# water_level.net
KiCad netlist of a schematic drawn in EAGLE
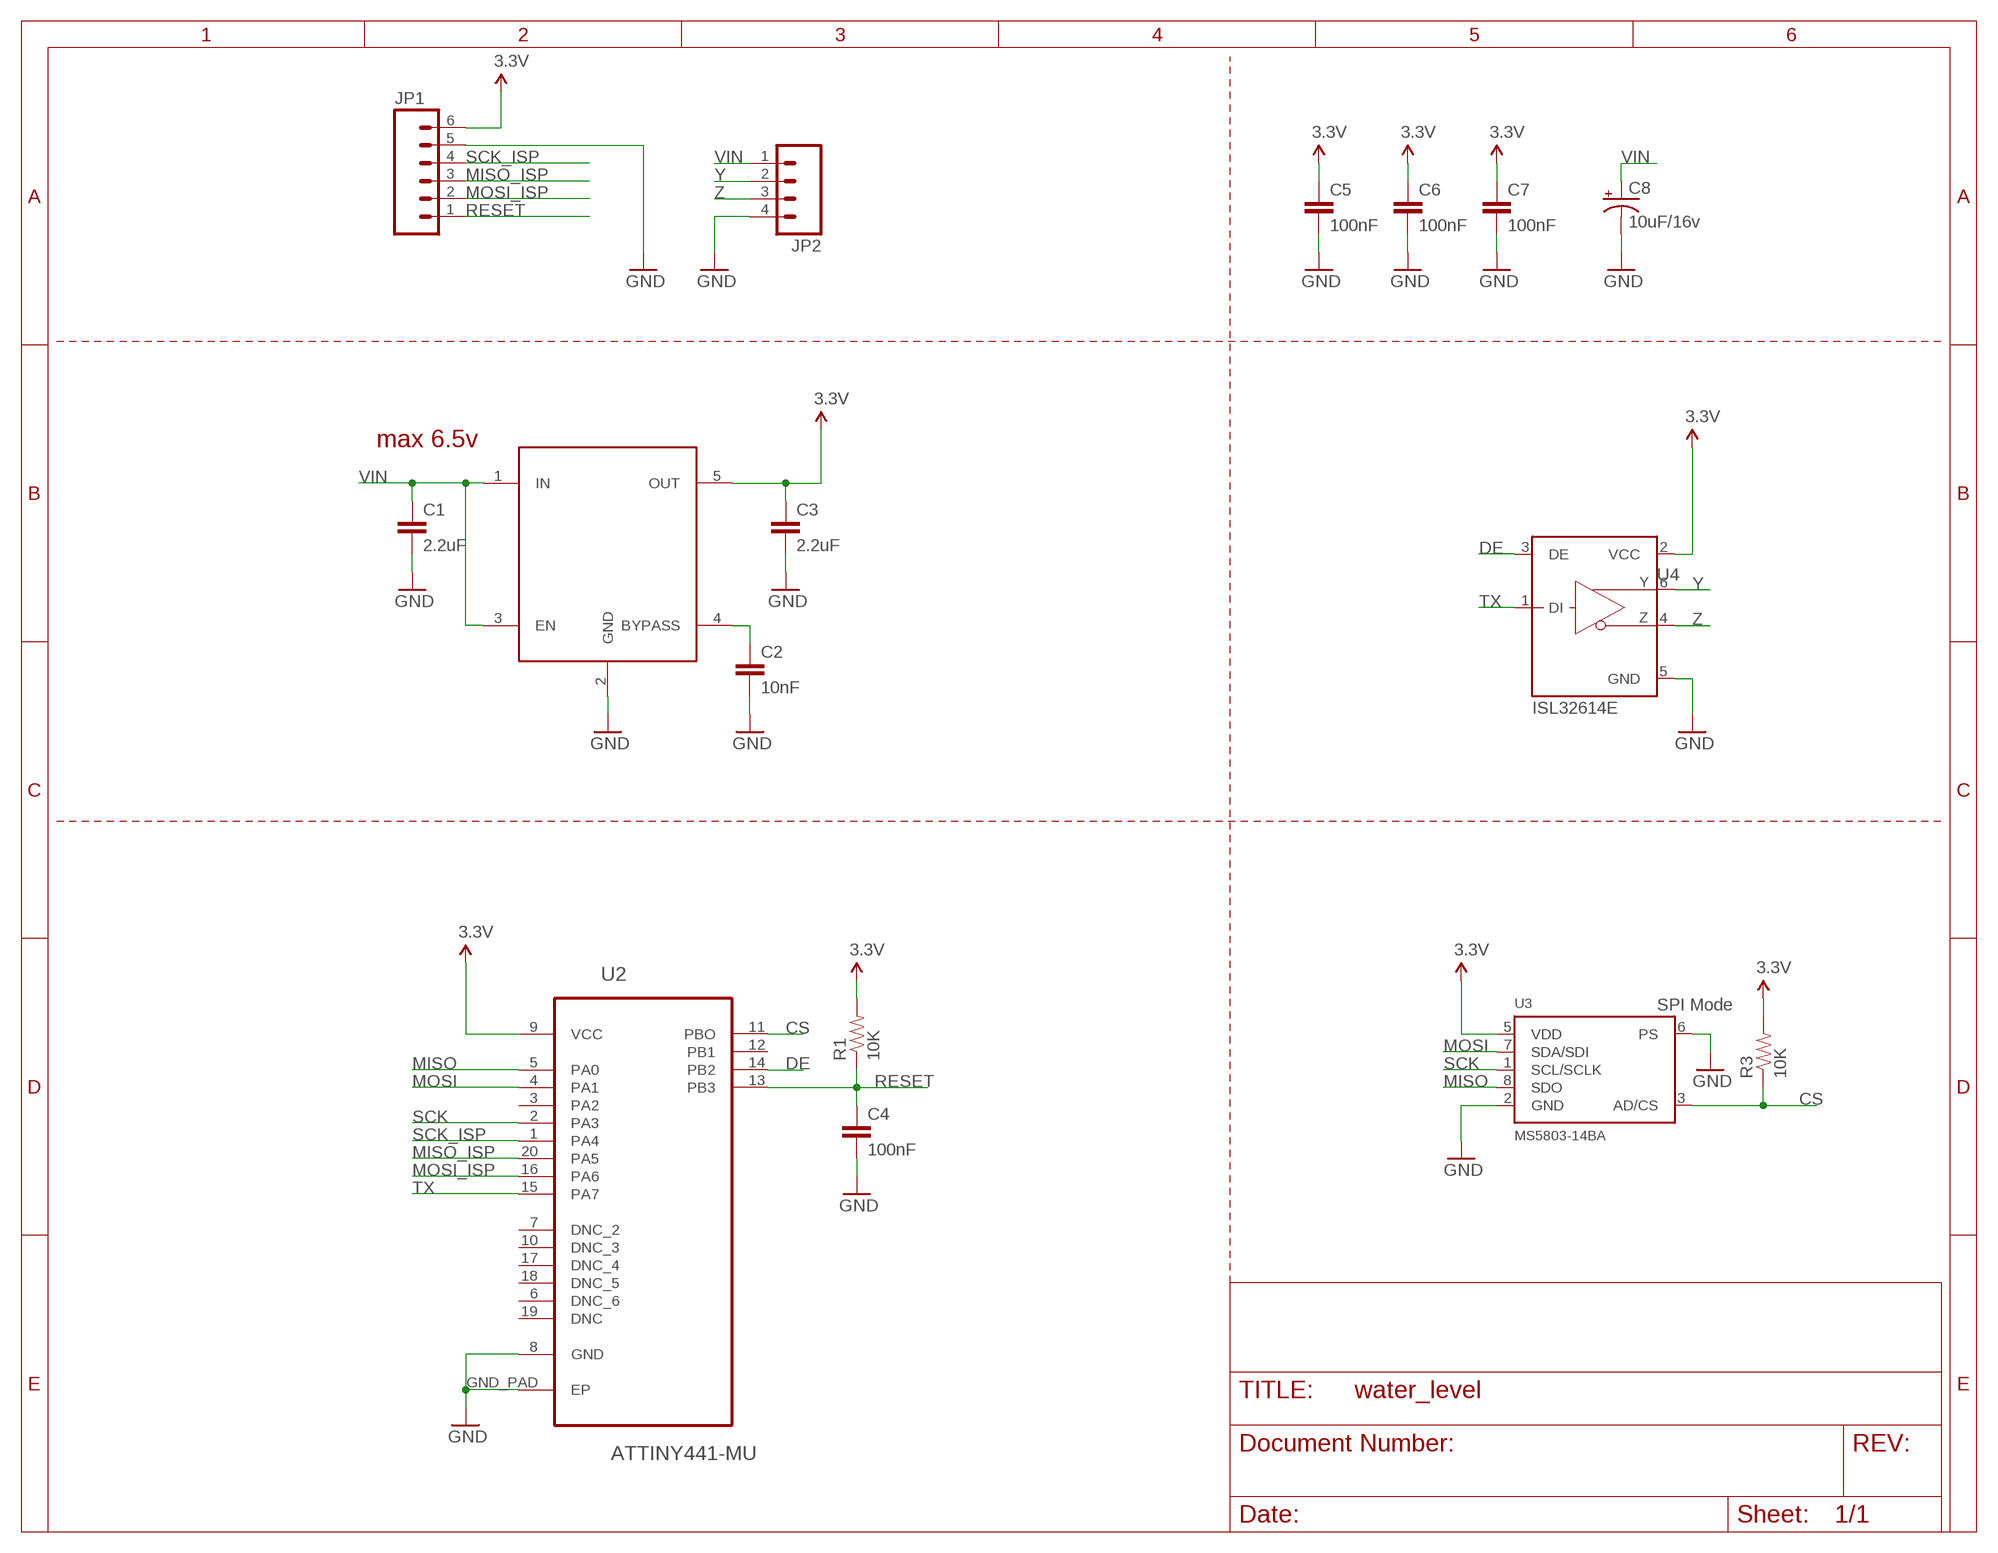
[diagram p0: schematic, sheet 1]

(export (version "E")
  (design (tool "Eeschema 10.0.6"))
  (components
    (comp (ref "C1")
      (value "2.2uF")
      (footprint "eagle-import:0402-CAP")
      (libsource (lib "eagle-import") (part "CAP0402-CAP"))
    )
    (comp (ref "C2")
      (value "10nF")
      (footprint "eagle-import:0402-CAP")
      (libsource (lib "eagle-import") (part "CAP0402-CAP"))
    )
    (comp (ref "C3")
      (value "2.2uF")
      (footprint "eagle-import:0402-CAP")
      (libsource (lib "eagle-import") (part "CAP0402-CAP"))
    )
    (comp (ref "C4")
      (value "100nF")
      (footprint "eagle-import:0402-CAP")
      (libsource (lib "eagle-import") (part "CAP0402-CAP"))
    )
    (comp (ref "C5")
      (value "100nF")
      (footprint "eagle-import:0402-CAP")
      (libsource (lib "eagle-import") (part "CAP0402-CAP"))
    )
    (comp (ref "C6")
      (value "100nF")
      (footprint "eagle-import:0402-CAP")
      (libsource (lib "eagle-import") (part "CAP0402-CAP"))
    )
    (comp (ref "C7")
      (value "100nF")
      (footprint "eagle-import:0402-CAP")
      (libsource (lib "eagle-import") (part "CAP0402-CAP"))
    )
    (comp (ref "C8")
      (value "10uF/16v")
      (footprint "eagle-import:EIA3216")
      (libsource (lib "eagle-import") (part "10UF-16V-10%(TANT)"))
    )
    (comp (ref "JP1")
      (value "M06SILK_FEMALE_PTH")
      (footprint "eagle-import:1X06")
      (libsource (lib "eagle-import") (part "M06SILK_FEMALE_PTH"))
    )
    (comp (ref "JP2")
      (value "M04PTH")
      (footprint "eagle-import:1X04")
      (libsource (lib "eagle-import") (part "M04PTH"))
    )
    (comp (ref "R1")
      (value "10K")
      (footprint "eagle-import:0402-RES")
      (libsource (lib "eagle-import") (part "RESISTOR0402"))
    )
    (comp (ref "R3")
      (value "10K")
      (footprint "eagle-import:0402-RES")
      (libsource (lib "eagle-import") (part "RESISTOR0402"))
    )
    (comp (ref "U1")
      (value "LP3985")
      (footprint "eagle-import:SOT23-5")
      (libsource (lib "eagle-import") (part "LP3985"))
    )
    (comp (ref "U2")
      (value "ATTINY441-MU")
      (footprint "eagle-import:QFN50P400X400X80-21N")
      (libsource (lib "eagle-import") (part "ATTINY441-MU"))
    )
    (comp (ref "U3")
      (value "MS5803-14BA")
      (footprint "eagle-import:MS5803")
      (libsource (lib "eagle-import") (part "MS5803-14BA"))
    )
    (comp (ref "U4")
      (value "ISL32614E")
      (footprint "eagle-import:SOT23-6")
      (libsource (lib "eagle-import") (part "ISL32614E"))
    )
  )
  (nets
    (net (code "1") (name "/CS") (class "Default")
      (node (ref "R3") (pin "1") (pinfunction "1_1") (pintype "passive"))
      (node (ref "U2") (pin "11") (pinfunction "PBO_11") (pintype "bidirectional"))
      (node (ref "U3") (pin "3") (pinfunction "AD/CS_3") (pintype "bidirectional"))
    )
    (net (code "2") (name "/DE") (class "Default")
      (node (ref "U2") (pin "14") (pinfunction "PB2_14") (pintype "bidirectional"))
      (node (ref "U4") (pin "3") (pinfunction "DE_3") (pintype "input"))
    )
    (net (code "3") (name "/MISO") (class "Default")
      (node (ref "U2") (pin "5") (pinfunction "PA0_5") (pintype "bidirectional"))
      (node (ref "U3") (pin "8") (pinfunction "SDO_8") (pintype "bidirectional"))
    )
    (net (code "4") (name "/MISO_ISP") (class "Default")
      (node (ref "JP1") (pin "3") (pinfunction "3_3") (pintype "passive"))
      (node (ref "U2") (pin "20") (pinfunction "PA5_20") (pintype "bidirectional"))
    )
    (net (code "5") (name "/MOSI") (class "Default")
      (node (ref "U2") (pin "4") (pinfunction "PA1_4") (pintype "bidirectional"))
      (node (ref "U3") (pin "7") (pinfunction "SDA/SDI_7") (pintype "bidirectional"))
    )
    (net (code "6") (name "/MOSI_ISP") (class "Default")
      (node (ref "JP1") (pin "2") (pinfunction "2_2") (pintype "passive"))
      (node (ref "U2") (pin "16") (pinfunction "PA6_16") (pintype "bidirectional"))
    )
    (net (code "7") (name "/RESET") (class "Default")
      (node (ref "C4") (pin "1") (pinfunction "1_1") (pintype "passive"))
      (node (ref "JP1") (pin "1") (pinfunction "1_1") (pintype "passive"))
      (node (ref "R1") (pin "1") (pinfunction "1_1") (pintype "passive"))
      (node (ref "U2") (pin "13") (pinfunction "PB3_13") (pintype "bidirectional"))
    )
    (net (code "8") (name "/SCK") (class "Default")
      (node (ref "U2") (pin "2") (pinfunction "PA3_2") (pintype "bidirectional"))
      (node (ref "U3") (pin "1") (pinfunction "SCL/SCLK_1") (pintype "bidirectional"))
    )
    (net (code "9") (name "/SCK_ISP") (class "Default")
      (node (ref "JP1") (pin "4") (pinfunction "4_4") (pintype "passive"))
      (node (ref "U2") (pin "1") (pinfunction "PA4_1") (pintype "bidirectional"))
    )
    (net (code "10") (name "/TX") (class "Default")
      (node (ref "U2") (pin "15") (pinfunction "PA7_15") (pintype "bidirectional"))
      (node (ref "U4") (pin "1") (pinfunction "DI_1") (pintype "input"))
    )
    (net (code "11") (name "/VIN") (class "Default")
      (node (ref "C1") (pin "1") (pinfunction "1_1") (pintype "passive"))
      (node (ref "C8") (pin "A") (pinfunction "+_A") (pintype "passive"))
      (node (ref "JP2") (pin "1") (pinfunction "1_1") (pintype "passive"))
      (node (ref "U1") (pin "1") (pinfunction "IN_1") (pintype "power_in"))
      (node (ref "U1") (pin "3") (pinfunction "EN_3") (pintype "input"))
    )
    (net (code "12") (name "/Y") (class "Default")
      (node (ref "JP2") (pin "2") (pinfunction "2_2") (pintype "passive"))
      (node (ref "U4") (pin "6") (pinfunction "Y_6") (pintype "passive"))
    )
    (net (code "13") (name "/Z") (class "Default")
      (node (ref "JP2") (pin "3") (pinfunction "3_3") (pintype "passive"))
      (node (ref "U4") (pin "4") (pinfunction "Z_4") (pintype "passive"))
    )
    (net (code "14") (name "3.3V") (class "Default")
      (node (ref "C3") (pin "1") (pinfunction "1_1") (pintype "passive"))
      (node (ref "C5") (pin "1") (pinfunction "1_1") (pintype "passive"))
      (node (ref "C6") (pin "1") (pinfunction "1_1") (pintype "passive"))
      (node (ref "C7") (pin "1") (pinfunction "1_1") (pintype "passive"))
      (node (ref "JP1") (pin "6") (pinfunction "6_6") (pintype "passive"))
      (node (ref "R1") (pin "2") (pinfunction "2_2") (pintype "passive"))
      (node (ref "R3") (pin "2") (pinfunction "2_2") (pintype "passive"))
      (node (ref "U1") (pin "5") (pinfunction "OUT_5") (pintype "power_in"))
      (node (ref "U2") (pin "9") (pinfunction "VCC_9") (pintype "power_in"))
      (node (ref "U3") (pin "5") (pinfunction "VDD_5") (pintype "bidirectional"))
      (node (ref "U4") (pin "2") (pinfunction "VCC_2") (pintype "power_in"))
    )
    (net (code "15") (name "GND") (class "Default")
      (node (ref "C1") (pin "2") (pinfunction "2_2") (pintype "passive"))
      (node (ref "C2") (pin "2") (pinfunction "2_2") (pintype "passive"))
      (node (ref "C3") (pin "2") (pinfunction "2_2") (pintype "passive"))
      (node (ref "C4") (pin "2") (pinfunction "2_2") (pintype "passive"))
      (node (ref "C5") (pin "2") (pinfunction "2_2") (pintype "passive"))
      (node (ref "C6") (pin "2") (pinfunction "2_2") (pintype "passive"))
      (node (ref "C7") (pin "2") (pinfunction "2_2") (pintype "passive"))
      (node (ref "C8") (pin "C") (pinfunction "-_C") (pintype "passive"))
      (node (ref "JP1") (pin "5") (pinfunction "5_5") (pintype "passive"))
      (node (ref "JP2") (pin "4") (pinfunction "4_4") (pintype "passive"))
      (node (ref "U1") (pin "2") (pinfunction "GND_2") (pintype "power_in"))
      (node (ref "U2") (pin "8") (pinfunction "GND_8") (pintype "passive"))
      (node (ref "U2") (pin "GND_PAD") (pinfunction "EP_GND_PAD") (pintype "passive"))
      (node (ref "U3") (pin "2") (pinfunction "GND_2") (pintype "bidirectional"))
      (node (ref "U3") (pin "6") (pinfunction "PS_6") (pintype "bidirectional"))
      (node (ref "U4") (pin "5") (pinfunction "GND_5") (pintype "power_in"))
    )
    (net (code "16") (name "Net-(U1-BYPASS)") (class "Default")
      (node (ref "C2") (pin "1") (pinfunction "1_1") (pintype "passive"))
      (node (ref "U1") (pin "4") (pinfunction "BYPASS_4") (pintype "output"))
    )
    (net (code "17") (name "unconnected-(U2-DNC-Pad19)") (class "Default")
      (node (ref "U2") (pin "19") (pinfunction "DNC_19") (pintype "no_connect"))
    )
    (net (code "18") (name "unconnected-(U2-DNC_2-Pad7)") (class "Default")
      (node (ref "U2") (pin "7") (pinfunction "DNC_2_7") (pintype "no_connect"))
    )
    (net (code "19") (name "unconnected-(U2-DNC_3-Pad10)") (class "Default")
      (node (ref "U2") (pin "10") (pinfunction "DNC_3_10") (pintype "no_connect"))
    )
    (net (code "20") (name "unconnected-(U2-DNC_4-Pad17)") (class "Default")
      (node (ref "U2") (pin "17") (pinfunction "DNC_4_17") (pintype "no_connect"))
    )
    (net (code "21") (name "unconnected-(U2-DNC_5-Pad18)") (class "Default")
      (node (ref "U2") (pin "18") (pinfunction "DNC_5_18") (pintype "no_connect"))
    )
    (net (code "22") (name "unconnected-(U2-DNC_6-Pad6)") (class "Default")
      (node (ref "U2") (pin "6") (pinfunction "DNC_6_6") (pintype "no_connect"))
    )
    (net (code "23") (name "unconnected-(U2-PA2-Pad3)") (class "Default")
      (node (ref "U2") (pin "3") (pinfunction "PA2_3") (pintype "bidirectional"))
    )
    (net (code "24") (name "unconnected-(U2-PB1-Pad12)") (class "Default")
      (node (ref "U2") (pin "12") (pinfunction "PB1_12") (pintype "bidirectional"))
    )
  )
)
